# EEM_connector.net
KiCad netlist of a schematic drawn in Altium Designer
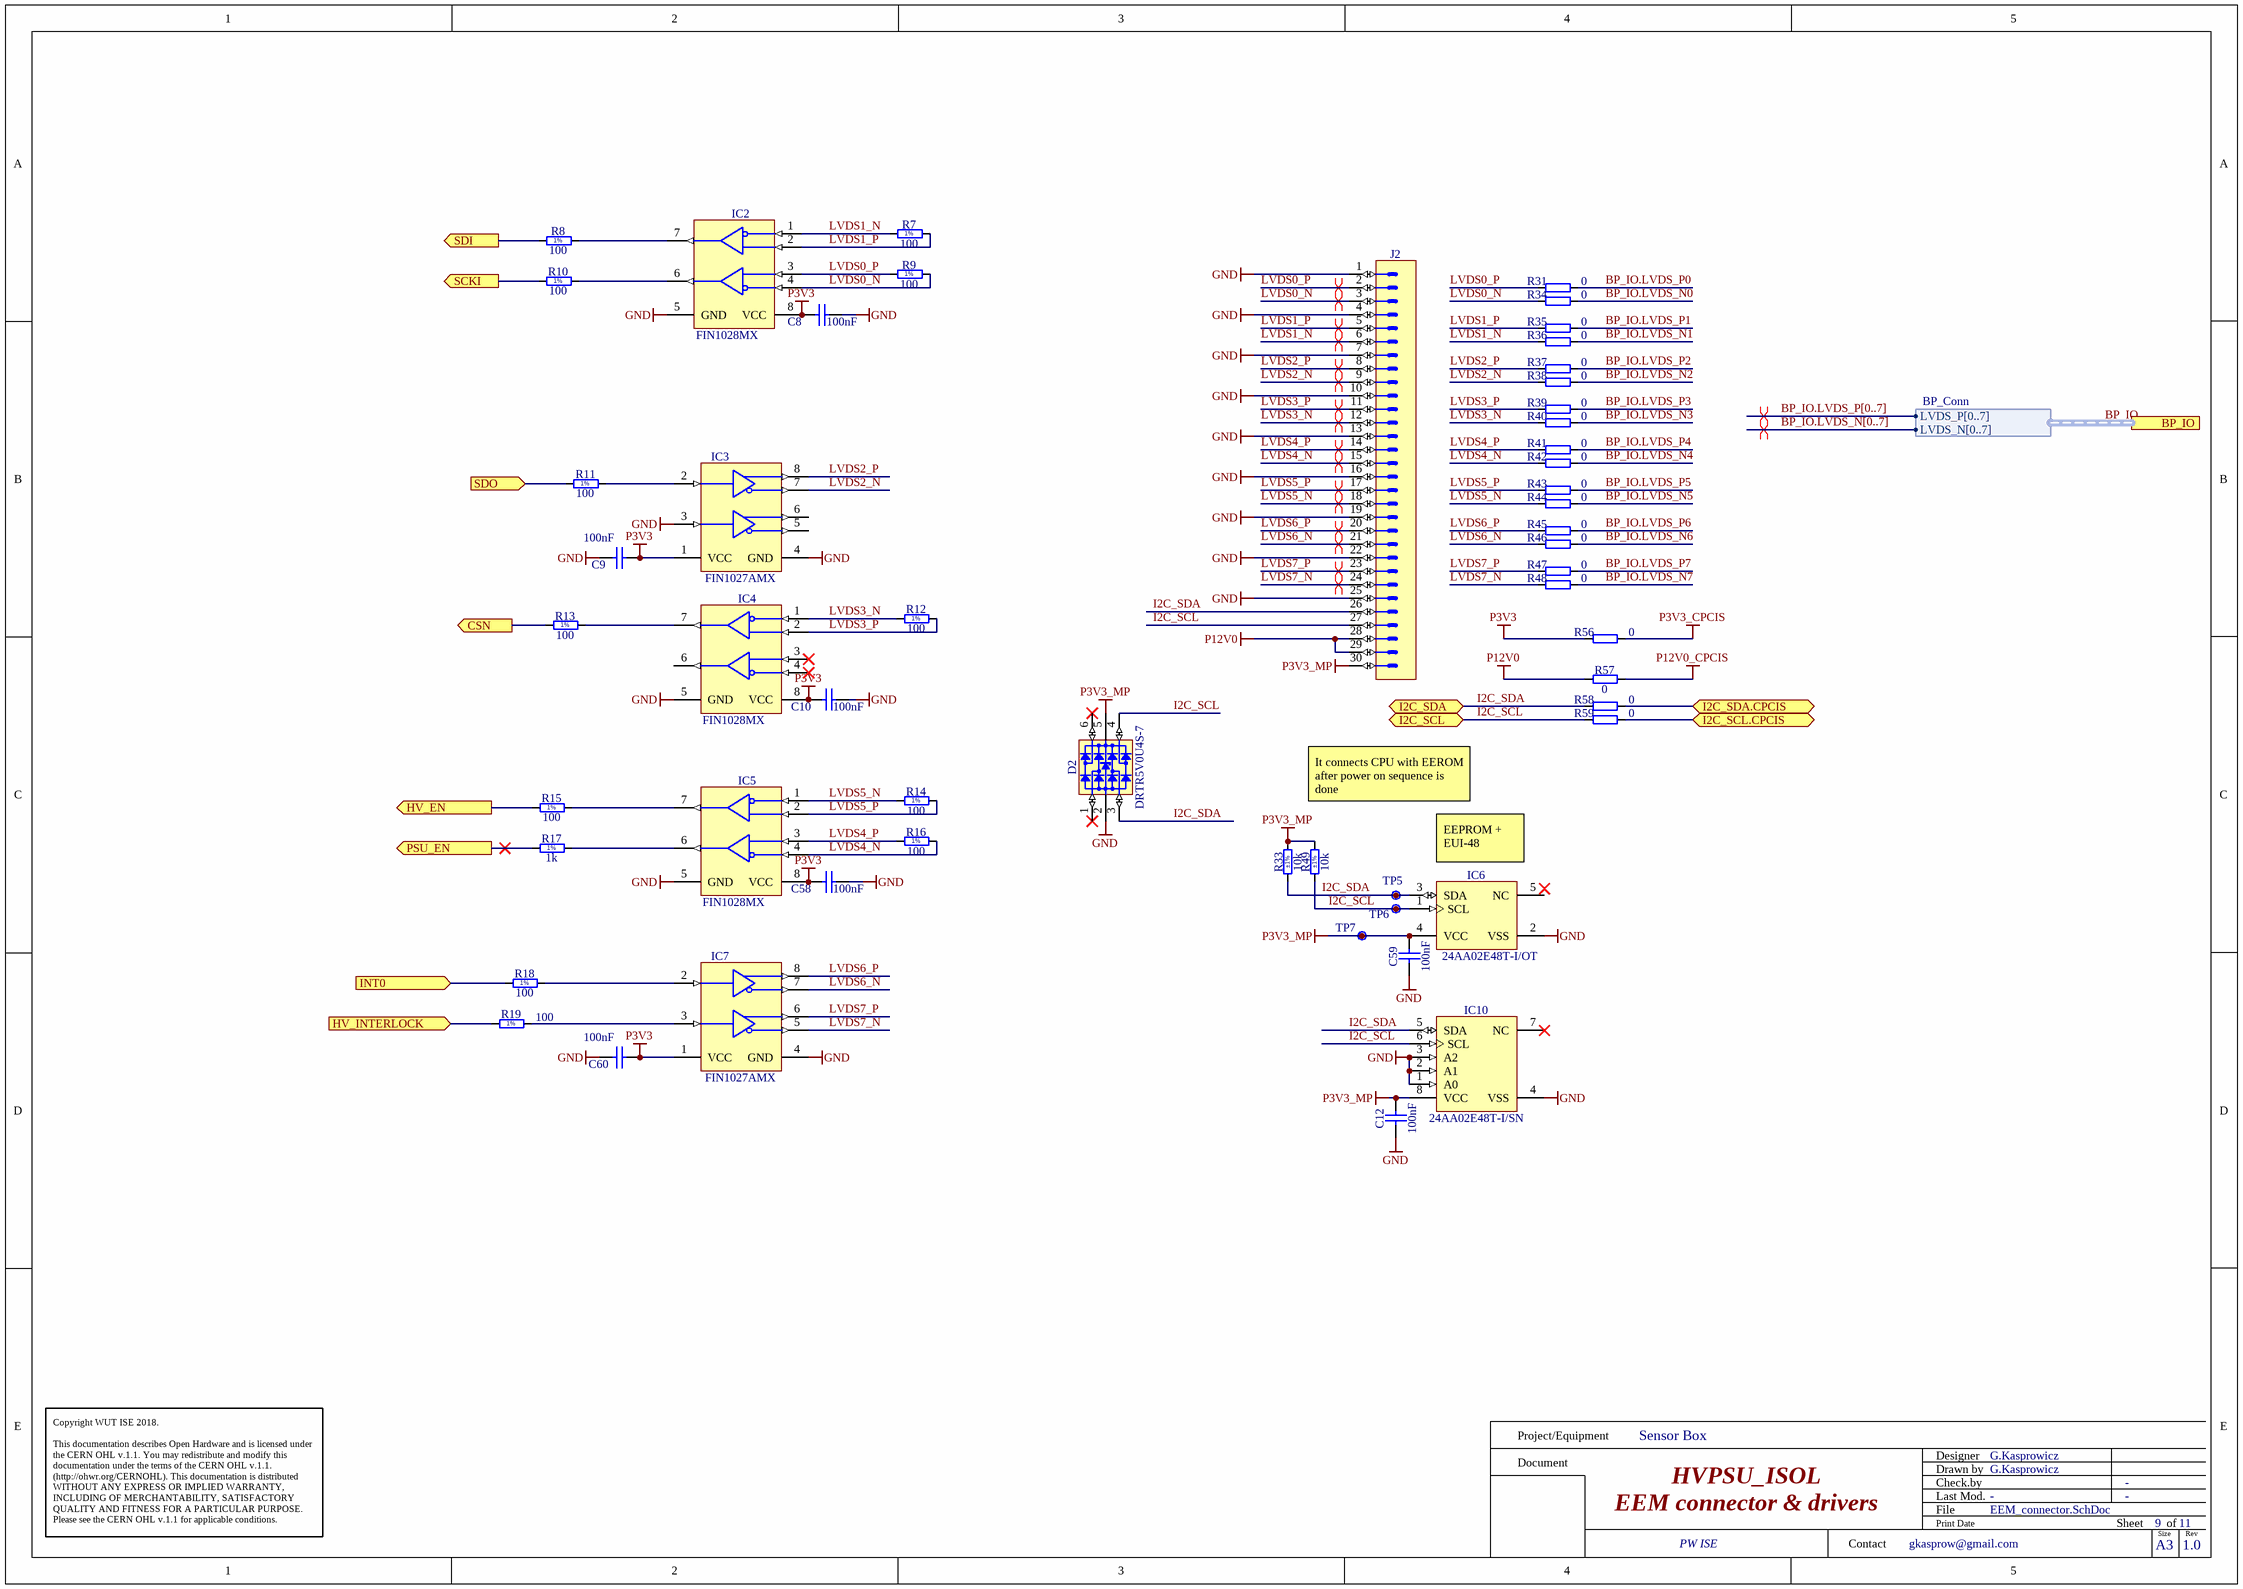
[diagram p0: EEM_connector.SchDoc]

(export (version "E")
  (design (tool "Eeschema 10.0.6"))
  (components
    (comp (ref "C8")
      (value "100nF")
      (footprint "CAPC1005X55N")
      (description "Non-polarised capacitor")
      (fields
        (field (name "PART NUMBER") "CC0402_100NF_16V_10%_X5R")
        (field (name "VOLTAGE") "16V")
        (field (name "AUTHOR") "CERN DEM JLC")
      )
      (libsource (lib "Capacitors") (part "Capacitor - non polarized"))
    )
    (comp (ref "C9")
      (value "100nF")
      (footprint "CAPC1005X55N")
      (description "Non-polarised capacitor")
      (fields
        (field (name "PART NUMBER") "CC0402_100NF_16V_10%_X5R")
        (field (name "VOLTAGE") "16V")
        (field (name "AUTHOR") "CERN DEM JLC")
      )
      (libsource (lib "Capacitors") (part "Capacitor - non polarized"))
    )
    (comp (ref "C10")
      (value "100nF")
      (footprint "CAPC1005X55N")
      (description "Non-polarised capacitor")
      (fields
        (field (name "PART NUMBER") "CC0402_100NF_16V_10%_X5R")
        (field (name "VOLTAGE") "16V")
        (field (name "AUTHOR") "CERN DEM JLC")
      )
      (libsource (lib "Capacitors") (part "Capacitor - non polarized"))
    )
    (comp (ref "C12")
      (value "100nF")
      (footprint "CAPC1005X55N")
      (description "Non-polarised capacitor")
      (fields
        (field (name "PART NUMBER") "CC0402_100NF_16V_10%_X5R")
        (field (name "VOLTAGE") "16V")
        (field (name "AUTHOR") "CERN DEM JLC")
      )
      (libsource (lib "Capacitors") (part "Capacitor - non polarized"))
    )
    (comp (ref "C58")
      (value "100nF")
      (footprint "CAPC1005X55N")
      (description "Non-polarised capacitor")
      (fields
        (field (name "PART NUMBER") "CC0402_100NF_16V_10%_X5R")
        (field (name "VOLTAGE") "16V")
        (field (name "AUTHOR") "CERN DEM JLC")
      )
      (libsource (lib "Capacitors") (part "Capacitor - non polarized"))
    )
    (comp (ref "C59")
      (value "100nF")
      (footprint "CAPC1005X55N")
      (description "Non-polarised capacitor")
      (fields
        (field (name "PART NUMBER") "CC0402_100NF_16V_10%_X5R")
        (field (name "VOLTAGE") "16V")
        (field (name "AUTHOR") "CERN DEM JLC")
      )
      (libsource (lib "Capacitors") (part "Capacitor - non polarized"))
    )
    (comp (ref "C60")
      (value "100nF")
      (footprint "CAPC1005X55N")
      (description "Non-polarised capacitor")
      (fields
        (field (name "PART NUMBER") "CC0402_100NF_16V_10%_X5R")
        (field (name "VOLTAGE") "16V")
        (field (name "AUTHOR") "CERN DEM JLC")
      )
      (libsource (lib "Capacitors") (part "Capacitor - non polarized"))
    )
    (comp (ref "D2")
      (value "DRTR5V0U4S-7")
      (footprint "SOT65P210X110-6N")
      (description "Integrated Quad Ultra-Low Capacitance ESD Protection")
      (fields (field (name "MANUFACTURER") "DIODES") (field (name "AUTHOR") "GK"))
      (libsource (lib "Diodes") (part "D_TVS_DRTR5V0U4S-7"))
    )
    (comp (ref "IC2")
      (value "FIN1028MX")
      (footprint "SOIC127P600X175-8N")
      (description "3.3V LVDS 2-Bit High-Speed Differential Reciever")
      (fields (field (name "MANUFACTURER") "ON Semiconductor") (field (name "AUTHOR") "GK"))
      (libsource (lib "LIBRARY_SCH") (part "IFC_FIN1028"))
    )
    (comp (ref "IC3")
      (value "FIN1027AMX")
      (footprint "SOIC127P600X175-8N")
      (description "3.3V LVDS, 2-Bit, High-Speed, Differential Driver")
      (fields (field (name "MANUFACTURER") "ON Semiconductor") (field (name "AUTHOR") "GK"))
      (libsource (lib "LIBRARY_SCH") (part "IFC_FIN1027A"))
    )
    (comp (ref "IC4")
      (value "FIN1028MX")
      (footprint "SOIC127P600X175-8N")
      (description "3.3V LVDS 2-Bit High-Speed Differential Reciever")
      (fields (field (name "MANUFACTURER") "ON Semiconductor") (field (name "AUTHOR") "GK"))
      (libsource (lib "LIBRARY_SCH") (part "IFC_FIN1028"))
    )
    (comp (ref "IC5")
      (value "FIN1028MX")
      (footprint "SOIC127P600X175-8N")
      (description "3.3V LVDS 2-Bit High-Speed Differential Reciever")
      (fields (field (name "MANUFACTURER") "ON Semiconductor") (field (name "AUTHOR") "GK"))
      (libsource (lib "LIBRARY_SCH") (part "IFC_FIN1028"))
    )
    (comp (ref "IC6")
      (value "24AA02E48T-I/OT")
      (footprint "SOT95P280X145-5N")
      (description "1.7V-5.5V, 2K I2C Serial EEPROM With EUI-48 Node Identity")
      (fields (field (name "MANUFACTURER") "MICROCHIP TECHNOLOGY") (field (name "AUTHOR") "CERN DEM MR"))
      (libsource (lib "ICs And Semiconductors") (part "24AA02E48T-I/OT"))
    )
    (comp (ref "IC7")
      (value "FIN1027AMX")
      (footprint "SOIC127P600X175-8N")
      (description "3.3V LVDS, 2-Bit, High-Speed, Differential Driver")
      (fields (field (name "MANUFACTURER") "ON Semiconductor") (field (name "AUTHOR") "GK"))
      (libsource (lib "LIBRARY_SCH") (part "IFC_FIN1027A"))
    )
    (comp (ref "IC10")
      (value "24AA02E48T-I/SN")
      (footprint "SOIC127P600X175-8N")
      (description "1.7V-5.5V, 2K I2C™ Serial EEPROMs with EUI-48™ Node Identity")
      (fields (field (name "MANUFACTURER") "MICROCHIP TECHNOLOGY") (field (name "AUTHOR") "CERN DEM MR"))
      (libsource (lib "ICs And Semiconductors") (part "24AA025E48-I/SN"))
    )
    (comp (ref "J2")
      (value "IDC")
      (footprint "3M_N2530-6002RB")
      (description "Connector 30 Male")
      (fields
        (field (name "PART NUMBER") "3M_N2530-6002RB")
        (field (name "MANUFACTURER") "3M")
        (field (name "AUTHOR") "CERN DEM JLC")
      )
      (libsource (lib "Connectors") (part "Connector 30 Male"))
    )
    (comp (ref "R7")
      (value "100")
      (footprint "RESC1005X40N")
      (description "Resistor - 1%")
      (fields
        (field (name "PART NUMBER") "R0402_100R_1%_0.0625W_100PPM")
        (field (name "POWER") "0.0625W")
        (field (name "AUTHOR") "CERN DEM JLC")
      )
      (libsource (lib "Resistors") (part "Resistor - 1%"))
    )
    (comp (ref "R8")
      (value "100")
      (footprint "RESC1005X40N")
      (description "Resistor - 1%")
      (fields
        (field (name "PART NUMBER") "R0402_100R_1%_0.0625W_100PPM")
        (field (name "POWER") "0.0625W")
        (field (name "AUTHOR") "CERN DEM JLC")
      )
      (libsource (lib "Resistors") (part "Resistor - 1%"))
    )
    (comp (ref "R9")
      (value "100")
      (footprint "RESC1005X40N")
      (description "Resistor - 1%")
      (fields
        (field (name "PART NUMBER") "R0402_100R_1%_0.0625W_100PPM")
        (field (name "POWER") "0.0625W")
        (field (name "AUTHOR") "CERN DEM JLC")
      )
      (libsource (lib "Resistors") (part "Resistor - 1%"))
    )
    (comp (ref "R10")
      (value "100")
      (footprint "RESC1005X40N")
      (description "Resistor - 1%")
      (fields
        (field (name "PART NUMBER") "R0402_100R_1%_0.0625W_100PPM")
        (field (name "POWER") "0.0625W")
        (field (name "AUTHOR") "CERN DEM JLC")
      )
      (libsource (lib "Resistors") (part "Resistor - 1%"))
    )
    (comp (ref "R11")
      (value "100")
      (footprint "RESC1005X40N")
      (description "Resistor - 1%")
      (fields
        (field (name "PART NUMBER") "R0402_100R_1%_0.0625W_100PPM")
        (field (name "POWER") "0.0625W")
        (field (name "AUTHOR") "CERN DEM JLC")
      )
      (libsource (lib "Resistors") (part "Resistor - 1%"))
    )
    (comp (ref "R12")
      (value "100")
      (footprint "RESC1005X40N")
      (description "Resistor - 1%")
      (fields
        (field (name "PART NUMBER") "R0402_100R_1%_0.0625W_100PPM")
        (field (name "POWER") "0.0625W")
        (field (name "AUTHOR") "CERN DEM JLC")
      )
      (libsource (lib "Resistors") (part "Resistor - 1%"))
    )
    (comp (ref "R13")
      (value "100")
      (footprint "RESC1005X40N")
      (description "Resistor - 1%")
      (fields
        (field (name "PART NUMBER") "R0402_100R_1%_0.0625W_100PPM")
        (field (name "POWER") "0.0625W")
        (field (name "AUTHOR") "CERN DEM JLC")
      )
      (libsource (lib "Resistors") (part "Resistor - 1%"))
    )
    (comp (ref "R14")
      (value "100")
      (footprint "RESC1005X40N")
      (description "Resistor - 1%")
      (fields
        (field (name "PART NUMBER") "R0402_100R_1%_0.0625W_100PPM")
        (field (name "POWER") "0.0625W")
        (field (name "AUTHOR") "CERN DEM JLC")
      )
      (libsource (lib "Resistors") (part "Resistor - 1%"))
    )
    (comp (ref "R15")
      (value "100")
      (footprint "RESC1005X40N")
      (description "Resistor - 1%")
      (fields
        (field (name "PART NUMBER") "R0402_100R_1%_0.0625W_100PPM")
        (field (name "POWER") "0.0625W")
        (field (name "AUTHOR") "CERN DEM JLC")
      )
      (libsource (lib "Resistors") (part "Resistor - 1%"))
    )
    (comp (ref "R16")
      (value "100")
      (footprint "RESC1005X40N")
      (description "Resistor - 1%")
      (fields
        (field (name "PART NUMBER") "R0402_100R_1%_0.0625W_100PPM")
        (field (name "POWER") "0.0625W")
        (field (name "AUTHOR") "CERN DEM JLC")
      )
      (libsource (lib "Resistors") (part "Resistor - 1%"))
    )
    (comp (ref "R17")
      (value "1k")
      (footprint "RESC1005X40N")
      (description "Resistor - 1%")
      (fields
        (field (name "PART NUMBER") "R0402_1K_1%_0.0625W_100PPM")
        (field (name "POWER") "0.0625W")
        (field (name "AUTHOR") "CERN DEM JLC")
      )
      (libsource (lib "Resistors") (part "Resistor - 1%"))
    )
    (comp (ref "R18")
      (value "100")
      (footprint "RESC1005X40N")
      (description "Resistor - 1%")
      (fields
        (field (name "PART NUMBER") "R0402_100R_1%_0.0625W_100PPM")
        (field (name "POWER") "0.0625W")
        (field (name "AUTHOR") "CERN DEM JLC")
      )
      (libsource (lib "Resistors") (part "Resistor - 1%"))
    )
    (comp (ref "R19")
      (value "100")
      (footprint "RESC1005X40N")
      (description "Resistor - 1%")
      (fields
        (field (name "PART NUMBER") "R0402_100R_1%_0.0625W_100PPM")
        (field (name "POWER") "0.0625W")
        (field (name "AUTHOR") "CERN DEM JLC")
      )
      (libsource (lib "Resistors") (part "Resistor - 1%"))
    )
    (comp (ref "R31")
      (value "0")
      (footprint "RESC1005X40N")
      (description "Resistor")
      (fields
        (field (name "PART NUMBER") "R0402_0R_JUMPER")
        (field (name "MANUFACTURER") "GENERIC")
        (field (name "AUTHOR") "CERN DEM JLC")
      )
      (libsource (lib "Resistors") (part "Resistor"))
    )
    (comp (ref "R33")
      (value "10k")
      (footprint "RESC1005X40N")
      (description "Resistor - 1%")
      (fields
        (field (name "TOLERANCE") "±1%")
        (field (name "PART NUMBER") "R0402_10K_1%_0.0625W_100PPM")
        (field (name "POWER") "0.0625W")
        (field (name "AUTHOR") "CERN DEM JLC")
      )
      (libsource (lib "Resistors") (part "Resistor - 1%"))
    )
    (comp (ref "R34")
      (value "0")
      (footprint "RESC1005X40N")
      (description "Resistor")
      (fields
        (field (name "PART NUMBER") "R0402_0R_JUMPER")
        (field (name "MANUFACTURER") "GENERIC")
        (field (name "AUTHOR") "CERN DEM JLC")
      )
      (libsource (lib "Resistors") (part "Resistor"))
    )
    (comp (ref "R35")
      (value "0")
      (footprint "RESC1005X40N")
      (description "Resistor")
      (fields
        (field (name "PART NUMBER") "R0402_0R_JUMPER")
        (field (name "MANUFACTURER") "GENERIC")
        (field (name "AUTHOR") "CERN DEM JLC")
      )
      (libsource (lib "Resistors") (part "Resistor"))
    )
    (comp (ref "R36")
      (value "0")
      (footprint "RESC1005X40N")
      (description "Resistor")
      (fields
        (field (name "PART NUMBER") "R0402_0R_JUMPER")
        (field (name "MANUFACTURER") "GENERIC")
        (field (name "AUTHOR") "CERN DEM JLC")
      )
      (libsource (lib "Resistors") (part "Resistor"))
    )
    (comp (ref "R37")
      (value "0")
      (footprint "RESC1005X40N")
      (description "Resistor")
      (fields
        (field (name "PART NUMBER") "R0402_0R_JUMPER")
        (field (name "MANUFACTURER") "GENERIC")
        (field (name "AUTHOR") "CERN DEM JLC")
      )
      (libsource (lib "Resistors") (part "Resistor"))
    )
    (comp (ref "R38")
      (value "0")
      (footprint "RESC1005X40N")
      (description "Resistor")
      (fields
        (field (name "PART NUMBER") "R0402_0R_JUMPER")
        (field (name "MANUFACTURER") "GENERIC")
        (field (name "AUTHOR") "CERN DEM JLC")
      )
      (libsource (lib "Resistors") (part "Resistor"))
    )
    (comp (ref "R39")
      (value "0")
      (footprint "RESC1005X40N")
      (description "Resistor")
      (fields
        (field (name "PART NUMBER") "R0402_0R_JUMPER")
        (field (name "MANUFACTURER") "GENERIC")
        (field (name "AUTHOR") "CERN DEM JLC")
      )
      (libsource (lib "Resistors") (part "Resistor"))
    )
    (comp (ref "R40")
      (value "0")
      (footprint "RESC1005X40N")
      (description "Resistor")
      (fields
        (field (name "PART NUMBER") "R0402_0R_JUMPER")
        (field (name "MANUFACTURER") "GENERIC")
        (field (name "AUTHOR") "CERN DEM JLC")
      )
      (libsource (lib "Resistors") (part "Resistor"))
    )
    (comp (ref "R41")
      (value "0")
      (footprint "RESC1005X40N")
      (description "Resistor")
      (fields
        (field (name "PART NUMBER") "R0402_0R_JUMPER")
        (field (name "MANUFACTURER") "GENERIC")
        (field (name "AUTHOR") "CERN DEM JLC")
      )
      (libsource (lib "Resistors") (part "Resistor"))
    )
    (comp (ref "R42")
      (value "0")
      (footprint "RESC1005X40N")
      (description "Resistor")
      (fields
        (field (name "PART NUMBER") "R0402_0R_JUMPER")
        (field (name "MANUFACTURER") "GENERIC")
        (field (name "AUTHOR") "CERN DEM JLC")
      )
      (libsource (lib "Resistors") (part "Resistor"))
    )
    (comp (ref "R43")
      (value "0")
      (footprint "RESC1005X40N")
      (description "Resistor")
      (fields
        (field (name "PART NUMBER") "R0402_0R_JUMPER")
        (field (name "MANUFACTURER") "GENERIC")
        (field (name "AUTHOR") "CERN DEM JLC")
      )
      (libsource (lib "Resistors") (part "Resistor"))
    )
    (comp (ref "R44")
      (value "0")
      (footprint "RESC1005X40N")
      (description "Resistor")
      (fields
        (field (name "PART NUMBER") "R0402_0R_JUMPER")
        (field (name "MANUFACTURER") "GENERIC")
        (field (name "AUTHOR") "CERN DEM JLC")
      )
      (libsource (lib "Resistors") (part "Resistor"))
    )
    (comp (ref "R45")
      (value "0")
      (footprint "RESC1005X40N")
      (description "Resistor")
      (fields
        (field (name "PART NUMBER") "R0402_0R_JUMPER")
        (field (name "MANUFACTURER") "GENERIC")
        (field (name "AUTHOR") "CERN DEM JLC")
      )
      (libsource (lib "Resistors") (part "Resistor"))
    )
    (comp (ref "R46")
      (value "0")
      (footprint "RESC1005X40N")
      (description "Resistor")
      (fields
        (field (name "PART NUMBER") "R0402_0R_JUMPER")
        (field (name "MANUFACTURER") "GENERIC")
        (field (name "AUTHOR") "CERN DEM JLC")
      )
      (libsource (lib "Resistors") (part "Resistor"))
    )
    (comp (ref "R47")
      (value "0")
      (footprint "RESC1005X40N")
      (description "Resistor")
      (fields
        (field (name "PART NUMBER") "R0402_0R_JUMPER")
        (field (name "MANUFACTURER") "GENERIC")
        (field (name "AUTHOR") "CERN DEM JLC")
      )
      (libsource (lib "Resistors") (part "Resistor"))
    )
    (comp (ref "R48")
      (value "0")
      (footprint "RESC1005X40N")
      (description "Resistor")
      (fields
        (field (name "PART NUMBER") "R0402_0R_JUMPER")
        (field (name "MANUFACTURER") "GENERIC")
        (field (name "AUTHOR") "CERN DEM JLC")
      )
      (libsource (lib "Resistors") (part "Resistor"))
    )
    (comp (ref "R49")
      (value "10k")
      (footprint "RESC1005X40N")
      (description "Resistor - 1%")
      (fields
        (field (name "TOLERANCE") "±1%")
        (field (name "PART NUMBER") "R0402_10K_1%_0.0625W_100PPM")
        (field (name "POWER") "0.0625W")
        (field (name "AUTHOR") "CERN DEM JLC")
      )
      (libsource (lib "Resistors") (part "Resistor - 1%"))
    )
    (comp (ref "R56")
      (value "0")
      (footprint "RESC1005X40N")
      (description "Resistor")
      (fields
        (field (name "PART NUMBER") "R0402_0R_JUMPER")
        (field (name "MANUFACTURER") "GENERIC")
        (field (name "AUTHOR") "CERN DEM JLC")
      )
      (libsource (lib "Resistors") (part "Resistor"))
    )
    (comp (ref "R57")
      (value "0")
      (footprint "RESC2012X60N")
      (description "Resistor")
      (fields
        (field (name "PART NUMBER") "R0805_0R_JUMPER")
        (field (name "MANUFACTURER") "GENERIC")
        (field (name "AUTHOR") "CERN DEM JLC")
      )
      (libsource (lib "Resistors") (part "Resistor"))
    )
    (comp (ref "R58")
      (value "0")
      (footprint "RESC1005X40N")
      (description "Resistor")
      (fields
        (field (name "PART NUMBER") "R0402_0R_JUMPER")
        (field (name "MANUFACTURER") "GENERIC")
        (field (name "AUTHOR") "CERN DEM JLC")
      )
      (libsource (lib "Resistors") (part "Resistor"))
    )
    (comp (ref "R59")
      (value "0")
      (footprint "RESC1005X40N")
      (description "Resistor")
      (fields
        (field (name "PART NUMBER") "R0402_0R_JUMPER")
        (field (name "MANUFACTURER") "GENERIC")
        (field (name "AUTHOR") "CERN DEM JLC")
      )
      (libsource (lib "Resistors") (part "Resistor"))
    )
    (comp (ref "TP5")
      (value "Test Point")
      (footprint "TPS127")
      (fields (field (name "PART NUMBER") "SMD_PAD_1.27X1.27MM") (field (name "AUTHOR") "CERN DEM JLC"))
      (libsource (lib "Eletro-mechanical") (part "Test Point"))
    )
    (comp (ref "TP6")
      (value "Test Point")
      (footprint "TPS127")
      (fields (field (name "PART NUMBER") "SMD_PAD_1.27X1.27MM") (field (name "AUTHOR") "CERN DEM JLC"))
      (libsource (lib "Eletro-mechanical") (part "Test Point"))
    )
    (comp (ref "TP7")
      (value "Test Point")
      (footprint "TPS127")
      (fields (field (name "PART NUMBER") "SMD_PAD_1.27X1.27MM") (field (name "AUTHOR") "CERN DEM JLC"))
      (libsource (lib "Eletro-mechanical") (part "Test Point"))
    )
  )
  (nets
    (net (code "2") (name "/BP_IO.LVDS_N0") (class "Default")
      (node (ref "R34") (pin "2") (pinfunction "2_2") (pintype "passive"))
    )
    (net (code "3") (name "/BP_IO.LVDS_N1") (class "Default")
      (node (ref "R36") (pin "2") (pinfunction "2_2") (pintype "passive"))
    )
    (net (code "4") (name "/BP_IO.LVDS_N2") (class "Default")
      (node (ref "R38") (pin "2") (pinfunction "2_2") (pintype "passive"))
    )
    (net (code "5") (name "/BP_IO.LVDS_N3") (class "Default")
      (node (ref "R40") (pin "2") (pinfunction "2_2") (pintype "passive"))
    )
    (net (code "6") (name "/BP_IO.LVDS_N4") (class "Default")
      (node (ref "R42") (pin "2") (pinfunction "2_2") (pintype "passive"))
    )
    (net (code "7") (name "/BP_IO.LVDS_N5") (class "Default")
      (node (ref "R44") (pin "2") (pinfunction "2_2") (pintype "passive"))
    )
    (net (code "8") (name "/BP_IO.LVDS_N6") (class "Default")
      (node (ref "R46") (pin "2") (pinfunction "2_2") (pintype "passive"))
    )
    (net (code "9") (name "/BP_IO.LVDS_N7") (class "Default")
      (node (ref "R48") (pin "2") (pinfunction "2_2") (pintype "passive"))
    )
    (net (code "10") (name "/BP_IO.LVDS_P0") (class "Default")
      (node (ref "R31") (pin "2") (pinfunction "2_2") (pintype "passive"))
    )
    (net (code "11") (name "/BP_IO.LVDS_P1") (class "Default")
      (node (ref "R35") (pin "2") (pinfunction "2_2") (pintype "passive"))
    )
    (net (code "12") (name "/BP_IO.LVDS_P2") (class "Default")
      (node (ref "R37") (pin "2") (pinfunction "2_2") (pintype "passive"))
    )
    (net (code "13") (name "/BP_IO.LVDS_P3") (class "Default")
      (node (ref "R39") (pin "2") (pinfunction "2_2") (pintype "passive"))
    )
    (net (code "14") (name "/BP_IO.LVDS_P4") (class "Default")
      (node (ref "R41") (pin "2") (pinfunction "2_2") (pintype "passive"))
    )
    (net (code "15") (name "/BP_IO.LVDS_P5") (class "Default")
      (node (ref "R43") (pin "2") (pinfunction "2_2") (pintype "passive"))
    )
    (net (code "16") (name "/BP_IO.LVDS_P6") (class "Default")
      (node (ref "R45") (pin "2") (pinfunction "2_2") (pintype "passive"))
    )
    (net (code "17") (name "/BP_IO.LVDS_P7") (class "Default")
      (node (ref "R47") (pin "2") (pinfunction "2_2") (pintype "passive"))
    )
    (net (code "19") (name "/CSN") (class "Default")
      (node (ref "R13") (pin "1") (pinfunction "1_1") (pintype "passive"))
    )
    (net (code "20") (name "/HV_EN") (class "Default")
      (node (ref "R15") (pin "1") (pinfunction "1_1") (pintype "passive"))
    )
    (net (code "21") (name "/HV_INTERLOCK") (class "Default")
      (node (ref "R19") (pin "1") (pinfunction "1_1") (pintype "passive"))
    )
    (net (code "22") (name "/I2C_SCL") (class "Default")
      (node (ref "D2") (pin "4") (pinfunction "I/O3_4") (pintype "bidirectional"))
      (node (ref "IC10") (pin "6") (pinfunction "SCL_6") (pintype "input"))
      (node (ref "IC6") (pin "1") (pinfunction "SCL_1") (pintype "input"))
      (node (ref "J2") (pin "27") (pinfunction "27_27") (pintype "bidirectional"))
      (node (ref "R49") (pin "1") (pinfunction "1_1") (pintype "passive"))
      (node (ref "R59") (pin "1") (pinfunction "1_1") (pintype "passive"))
      (node (ref "TP6") (pin "1") (pinfunction "1_1") (pintype "bidirectional"))
    )
    (net (code "23") (name "/I2C_SCL.CPCIS") (class "Default")
      (node (ref "R59") (pin "2") (pinfunction "2_2") (pintype "passive"))
    )
    (net (code "24") (name "/I2C_SDA") (class "Default")
      (node (ref "D2") (pin "3") (pinfunction "I/O2_3") (pintype "bidirectional"))
      (node (ref "IC10") (pin "5") (pinfunction "SDA_5") (pintype "bidirectional"))
      (node (ref "IC6") (pin "3") (pinfunction "SDA_3") (pintype "bidirectional"))
      (node (ref "J2") (pin "26") (pinfunction "26_26") (pintype "bidirectional"))
      (node (ref "R33") (pin "1") (pinfunction "1_1") (pintype "passive"))
      (node (ref "R58") (pin "1") (pinfunction "1_1") (pintype "passive"))
      (node (ref "TP5") (pin "1") (pinfunction "1_1") (pintype "bidirectional"))
    )
    (net (code "25") (name "/I2C_SDA.CPCIS") (class "Default")
      (node (ref "R58") (pin "2") (pinfunction "2_2") (pintype "passive"))
    )
    (net (code "26") (name "/INT0") (class "Default")
      (node (ref "R18") (pin "1") (pinfunction "1_1") (pintype "passive"))
    )
    (net (code "27") (name "/LVDS0_N") (class "Default")
      (node (ref "IC2") (pin "4") (pinfunction "RIN2-_4") (pintype "input"))
      (node (ref "J2") (pin "3") (pinfunction "3_3") (pintype "bidirectional"))
      (node (ref "R34") (pin "1") (pinfunction "1_1") (pintype "passive"))
      (node (ref "R9") (pin "2") (pinfunction "2_2") (pintype "passive"))
    )
    (net (code "28") (name "/LVDS0_P") (class "Default")
      (node (ref "IC2") (pin "3") (pinfunction "RIN2+_3") (pintype "input"))
      (node (ref "J2") (pin "2") (pinfunction "2_2") (pintype "bidirectional"))
      (node (ref "R31") (pin "1") (pinfunction "1_1") (pintype "passive"))
      (node (ref "R9") (pin "1") (pinfunction "1_1") (pintype "passive"))
    )
    (net (code "29") (name "/LVDS1_N") (class "Default")
      (node (ref "IC2") (pin "1") (pinfunction "RIN1-_1") (pintype "input"))
      (node (ref "J2") (pin "6") (pinfunction "6_6") (pintype "bidirectional"))
      (node (ref "R36") (pin "1") (pinfunction "1_1") (pintype "passive"))
      (node (ref "R7") (pin "1") (pinfunction "1_1") (pintype "passive"))
    )
    (net (code "30") (name "/LVDS1_P") (class "Default")
      (node (ref "IC2") (pin "2") (pinfunction "RIN1+_2") (pintype "input"))
      (node (ref "J2") (pin "5") (pinfunction "5_5") (pintype "bidirectional"))
      (node (ref "R35") (pin "1") (pinfunction "1_1") (pintype "passive"))
      (node (ref "R7") (pin "2") (pinfunction "2_2") (pintype "passive"))
    )
    (net (code "31") (name "/LVDS2_N") (class "Default")
      (node (ref "IC3") (pin "7") (pinfunction "DOUT-_7") (pintype "output"))
      (node (ref "J2") (pin "9") (pinfunction "9_9") (pintype "bidirectional"))
      (node (ref "R38") (pin "1") (pinfunction "1_1") (pintype "passive"))
    )
    (net (code "32") (name "/LVDS2_P") (class "Default")
      (node (ref "IC3") (pin "8") (pinfunction "DOUT+_8") (pintype "output"))
      (node (ref "J2") (pin "8") (pinfunction "8_8") (pintype "bidirectional"))
      (node (ref "R37") (pin "1") (pinfunction "1_1") (pintype "passive"))
    )
    (net (code "33") (name "/LVDS3_N") (class "Default")
      (node (ref "IC4") (pin "1") (pinfunction "RIN1-_1") (pintype "input"))
      (node (ref "J2") (pin "12") (pinfunction "12_12") (pintype "bidirectional"))
      (node (ref "R12") (pin "1") (pinfunction "1_1") (pintype "passive"))
      (node (ref "R40") (pin "1") (pinfunction "1_1") (pintype "passive"))
    )
    (net (code "34") (name "/LVDS3_P") (class "Default")
      (node (ref "IC4") (pin "2") (pinfunction "RIN1+_2") (pintype "input"))
      (node (ref "J2") (pin "11") (pinfunction "11_11") (pintype "bidirectional"))
      (node (ref "R12") (pin "2") (pinfunction "2_2") (pintype "passive"))
      (node (ref "R39") (pin "1") (pinfunction "1_1") (pintype "passive"))
    )
    (net (code "35") (name "/LVDS4_N") (class "Default")
      (node (ref "IC5") (pin "4") (pinfunction "RIN2-_4") (pintype "input"))
      (node (ref "J2") (pin "15") (pinfunction "15_15") (pintype "bidirectional"))
      (node (ref "R16") (pin "2") (pinfunction "2_2") (pintype "passive"))
      (node (ref "R42") (pin "1") (pinfunction "1_1") (pintype "passive"))
    )
    (net (code "36") (name "/LVDS4_P") (class "Default")
      (node (ref "IC5") (pin "3") (pinfunction "RIN2+_3") (pintype "input"))
      (node (ref "J2") (pin "14") (pinfunction "14_14") (pintype "bidirectional"))
      (node (ref "R16") (pin "1") (pinfunction "1_1") (pintype "passive"))
      (node (ref "R41") (pin "1") (pinfunction "1_1") (pintype "passive"))
    )
    (net (code "37") (name "/LVDS5_N") (class "Default")
      (node (ref "IC5") (pin "1") (pinfunction "RIN1-_1") (pintype "input"))
      (node (ref "J2") (pin "18") (pinfunction "18_18") (pintype "bidirectional"))
      (node (ref "R14") (pin "1") (pinfunction "1_1") (pintype "passive"))
      (node (ref "R44") (pin "1") (pinfunction "1_1") (pintype "passive"))
    )
    (net (code "38") (name "/LVDS5_P") (class "Default")
      (node (ref "IC5") (pin "2") (pinfunction "RIN1+_2") (pintype "input"))
      (node (ref "J2") (pin "17") (pinfunction "17_17") (pintype "bidirectional"))
      (node (ref "R14") (pin "2") (pinfunction "2_2") (pintype "passive"))
      (node (ref "R43") (pin "1") (pinfunction "1_1") (pintype "passive"))
    )
    (net (code "39") (name "/LVDS6_N") (class "Default")
      (node (ref "IC7") (pin "7") (pinfunction "DOUT-_7") (pintype "output"))
      (node (ref "J2") (pin "21") (pinfunction "21_21") (pintype "bidirectional"))
      (node (ref "R46") (pin "1") (pinfunction "1_1") (pintype "passive"))
    )
    (net (code "40") (name "/LVDS6_P") (class "Default")
      (node (ref "IC7") (pin "8") (pinfunction "DOUT+_8") (pintype "output"))
      (node (ref "J2") (pin "20") (pinfunction "20_20") (pintype "bidirectional"))
      (node (ref "R45") (pin "1") (pinfunction "1_1") (pintype "passive"))
    )
    (net (code "41") (name "/LVDS7_N") (class "Default")
      (node (ref "IC7") (pin "5") (pinfunction "DOUT-_5") (pintype "output"))
      (node (ref "J2") (pin "24") (pinfunction "24_24") (pintype "bidirectional"))
      (node (ref "R48") (pin "1") (pinfunction "1_1") (pintype "passive"))
    )
    (net (code "42") (name "/LVDS7_P") (class "Default")
      (node (ref "IC7") (pin "6") (pinfunction "DOUT+_6") (pintype "output"))
      (node (ref "J2") (pin "23") (pinfunction "23_23") (pintype "bidirectional"))
      (node (ref "R47") (pin "1") (pinfunction "1_1") (pintype "passive"))
    )
    (net (code "43") (name "/PSU_EN") (class "Default")
      (node (ref "R17") (pin "1") (pinfunction "1_1") (pintype "passive"))
    )
    (net (code "44") (name "/SCKI") (class "Default")
      (node (ref "R10") (pin "1") (pinfunction "1_1") (pintype "passive"))
    )
    (net (code "45") (name "/SDI") (class "Default")
      (node (ref "R8") (pin "1") (pinfunction "1_1") (pintype "passive"))
    )
    (net (code "46") (name "/SDO") (class "Default")
      (node (ref "R11") (pin "1") (pinfunction "1_1") (pintype "passive"))
    )
    (net (code "48") (name "GND") (class "Default")
      (node (ref "C10") (pin "1") (pinfunction "1_1") (pintype "passive"))
      (node (ref "C12") (pin "1") (pinfunction "1_1") (pintype "passive"))
      (node (ref "C58") (pin "1") (pinfunction "1_1") (pintype "passive"))
      (node (ref "C59") (pin "1") (pinfunction "1_1") (pintype "passive"))
      (node (ref "C60") (pin "1") (pinfunction "1_1") (pintype "passive"))
      (node (ref "C8") (pin "1") (pinfunction "1_1") (pintype "passive"))
      (node (ref "C9") (pin "1") (pinfunction "1_1") (pintype "passive"))
      (node (ref "D2") (pin "2") (pinfunction "GND_2") (pintype "power_in"))
      (node (ref "IC10") (pin "1") (pinfunction "A0_1") (pintype "input"))
      (node (ref "IC10") (pin "2") (pinfunction "A1_2") (pintype "input"))
      (node (ref "IC10") (pin "3") (pinfunction "A2_3") (pintype "input"))
      (node (ref "IC10") (pin "4") (pinfunction "VSS_4") (pintype "power_in"))
      (node (ref "IC2") (pin "5") (pinfunction "GND_5") (pintype "power_in"))
      (node (ref "IC3") (pin "3") (pinfunction "DIN2RIN-_3") (pintype "input"))
      (node (ref "IC3") (pin "4") (pinfunction "GND_4") (pintype "power_in"))
      (node (ref "IC4") (pin "5") (pinfunction "GND_5") (pintype "power_in"))
      (node (ref "IC5") (pin "5") (pinfunction "GND_5") (pintype "power_in"))
      (node (ref "IC6") (pin "2") (pinfunction "VSS_2") (pintype "power_in"))
      (node (ref "IC7") (pin "4") (pinfunction "GND_4") (pintype "power_in"))
      (node (ref "J2") (pin "1") (pinfunction "1_1") (pintype "bidirectional"))
      (node (ref "J2") (pin "10") (pinfunction "10_10") (pintype "bidirectional"))
      (node (ref "J2") (pin "13") (pinfunction "13_13") (pintype "bidirectional"))
      (node (ref "J2") (pin "16") (pinfunction "16_16") (pintype "bidirectional"))
      (node (ref "J2") (pin "19") (pinfunction "19_19") (pintype "bidirectional"))
      (node (ref "J2") (pin "22") (pinfunction "22_22") (pintype "bidirectional"))
      (node (ref "J2") (pin "25") (pinfunction "25_25") (pintype "bidirectional"))
      (node (ref "J2") (pin "4") (pinfunction "4_4") (pintype "bidirectional"))
      (node (ref "J2") (pin "7") (pinfunction "7_7") (pintype "bidirectional"))
    )
    (net (code "49") (name "Net-(IC2-ROUT1)") (class "Default")
      (node (ref "IC2") (pin "7") (pinfunction "ROUT1_7") (pintype "output"))
      (node (ref "R8") (pin "2") (pinfunction "2_2") (pintype "passive"))
    )
    (net (code "50") (name "Net-(IC2-ROUT2)") (class "Default")
      (node (ref "IC2") (pin "6") (pinfunction "ROUT2_6") (pintype "output"))
      (node (ref "R10") (pin "2") (pinfunction "2_2") (pintype "passive"))
    )
    (net (code "51") (name "Net-(IC3-DIN1)") (class "Default")
      (node (ref "IC3") (pin "2") (pinfunction "DIN1_2") (pintype "input"))
      (node (ref "R11") (pin "2") (pinfunction "2_2") (pintype "passive"))
    )
    (net (code "52") (name "Net-(IC4-ROUT1)") (class "Default")
      (node (ref "IC4") (pin "7") (pinfunction "ROUT1_7") (pintype "output"))
      (node (ref "R13") (pin "2") (pinfunction "2_2") (pintype "passive"))
    )
    (net (code "53") (name "Net-(IC5-ROUT1)") (class "Default")
      (node (ref "IC5") (pin "7") (pinfunction "ROUT1_7") (pintype "output"))
      (node (ref "R15") (pin "2") (pinfunction "2_2") (pintype "passive"))
    )
    (net (code "54") (name "Net-(IC5-ROUT2)") (class "Default")
      (node (ref "IC5") (pin "6") (pinfunction "ROUT2_6") (pintype "output"))
      (node (ref "R17") (pin "2") (pinfunction "2_2") (pintype "passive"))
    )
    (net (code "55") (name "Net-(IC7-DIN1)") (class "Default")
      (node (ref "IC7") (pin "2") (pinfunction "DIN1_2") (pintype "input"))
      (node (ref "R18") (pin "2") (pinfunction "2_2") (pintype "passive"))
    )
    (net (code "56") (name "Net-(IC7-DIN2RIN-)") (class "Default")
      (node (ref "IC7") (pin "3") (pinfunction "DIN2RIN-_3") (pintype "input"))
      (node (ref "R19") (pin "2") (pinfunction "2_2") (pintype "passive"))
    )
    (net (code "57") (name "P3V3") (class "Default")
      (node (ref "C10") (pin "2") (pinfunction "2_2") (pintype "passive"))
      (node (ref "C58") (pin "2") (pinfunction "2_2") (pintype "passive"))
      (node (ref "C60") (pin "2") (pinfunction "2_2") (pintype "passive"))
      (node (ref "C8") (pin "2") (pinfunction "2_2") (pintype "passive"))
      (node (ref "C9") (pin "2") (pinfunction "2_2") (pintype "passive"))
      (node (ref "IC2") (pin "8") (pinfunction "VCC_8") (pintype "power_in"))
      (node (ref "IC3") (pin "1") (pinfunction "VCC_1") (pintype "power_in"))
      (node (ref "IC4") (pin "8") (pinfunction "VCC_8") (pintype "power_in"))
      (node (ref "IC5") (pin "8") (pinfunction "VCC_8") (pintype "power_in"))
      (node (ref "IC7") (pin "1") (pinfunction "VCC_1") (pintype "power_in"))
      (node (ref "R56") (pin "1") (pinfunction "1_1") (pintype "passive"))
    )
    (net (code "58") (name "P3V3_CPCIS") (class "Default")
      (node (ref "R56") (pin "2") (pinfunction "2_2") (pintype "passive"))
    )
    (net (code "59") (name "P3V3_MP") (class "Default")
      (node (ref "C12") (pin "2") (pinfunction "2_2") (pintype "passive"))
      (node (ref "C59") (pin "2") (pinfunction "2_2") (pintype "passive"))
      (node (ref "D2") (pin "5") (pinfunction "VBUS_5") (pintype "power_in"))
      (node (ref "IC10") (pin "8") (pinfunction "VCC_8") (pintype "power_in"))
      (node (ref "IC6") (pin "4") (pinfunction "VCC_4") (pintype "power_in"))
      (node (ref "J2") (pin "30") (pinfunction "30_30") (pintype "bidirectional"))
      (node (ref "R33") (pin "2") (pinfunction "2_2") (pintype "passive"))
      (node (ref "R49") (pin "2") (pinfunction "2_2") (pintype "passive"))
      (node (ref "TP7") (pin "1") (pinfunction "1_1") (pintype "bidirectional"))
    )
    (net (code "60") (name "P12V0") (class "Default")
      (node (ref "J2") (pin "28") (pinfunction "28_28") (pintype "bidirectional"))
      (node (ref "J2") (pin "29") (pinfunction "29_29") (pintype "bidirectional"))
      (node (ref "R57") (pin "1") (pinfunction "1_1") (pintype "passive"))
    )
    (net (code "61") (name "P12V0_CPCIS") (class "Default")
      (node (ref "R57") (pin "2") (pinfunction "2_2") (pintype "passive"))
    )
    (net (code "62") (name "unconnected-(D2-I{slash}O1-Pad1)") (class "Default")
      (node (ref "D2") (pin "1") (pinfunction "I/O1_1") (pintype "bidirectional+no_connect"))
    )
    (net (code "63") (name "unconnected-(D2-I{slash}O4-Pad6)") (class "Default")
      (node (ref "D2") (pin "6") (pinfunction "I/O4_6") (pintype "bidirectional+no_connect"))
    )
    (net (code "64") (name "unconnected-(IC3-DOUT+-Pad6)") (class "Default")
      (node (ref "IC3") (pin "6") (pinfunction "DOUT+_6") (pintype "output"))
    )
    (net (code "65") (name "unconnected-(IC3-DOUT--Pad5)") (class "Default")
      (node (ref "IC3") (pin "5") (pinfunction "DOUT-_5") (pintype "output"))
    )
    (net (code "66") (name "unconnected-(IC4-RIN2+-Pad3)") (class "Default")
      (node (ref "IC4") (pin "3") (pinfunction "RIN2+_3") (pintype "input+no_connect"))
    )
    (net (code "67") (name "unconnected-(IC4-RIN2--Pad4)") (class "Default")
      (node (ref "IC4") (pin "4") (pinfunction "RIN2-_4") (pintype "input+no_connect"))
    )
    (net (code "68") (name "unconnected-(IC4-ROUT2-Pad6)") (class "Default")
      (node (ref "IC4") (pin "6") (pinfunction "ROUT2_6") (pintype "output"))
    )
    (net (code "69") (name "unconnected-(IC6-NC-Pad5)") (class "Default")
      (node (ref "IC6") (pin "5") (pinfunction "NC_5") (pintype "passive"))
    )
    (net (code "70") (name "unconnected-(IC10-NC-Pad7)") (class "Default")
      (node (ref "IC10") (pin "7") (pinfunction "NC_7") (pintype "passive+no_connect"))
    )
  )
)
